# SheetPower.net
KiCad netlist of a schematic drawn in Altium Designer
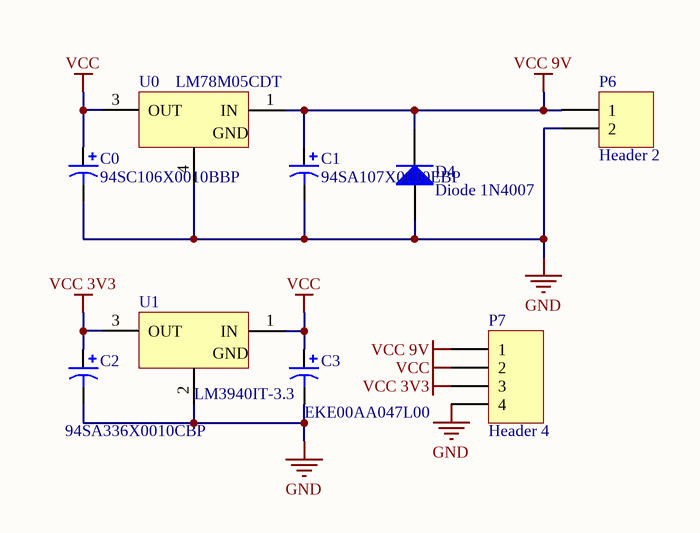
[diagram p0: SheetPower.SchDoc]

(export (version "E")
  (design (tool "Eeschema 10.0.6"))
  (components
    (comp (ref "C0")
      (value "94SC106X0010BBP")
      (footprint "B")
      (description "Solid Aluminum Capacitor with Organic Semiconductor Electrolyte: 10uF, 10V, Bulk Pack")
      (fields (field (name "PUBLISHER") "Altium Limited"))
      (libsource (lib "Vishay Electrolytic Radial-Lead Capacitor") (part "94SC106X0010BBP"))
    )
    (comp (ref "C1")
      (value "94SA107X0010EBP")
      (footprint "E")
      (description "Solid Aluminum Capacitor with Organic Semiconductor Electrolyte: 100uF, 10V, Bulk Pack")
      (fields (field (name "PUBLISHER") "Altium Limited"))
      (libsource (lib "Vishay Electrolytic Radial-Lead Capacitor") (part "94SA107X0010EBP"))
    )
    (comp (ref "C2")
      (value "94SA336X0010CBP")
      (footprint "C")
      (description "Solid Aluminum Capacitor with Organic Semiconductor Electrolyte: 33uF, 10V, Bulk Pack")
      (fields (field (name "PUBLISHER") "Altium Limited"))
      (libsource (lib "Vishay Electrolytic Radial-Lead Capacitor") (part "94SA336X0010CBP"))
    )
    (comp (ref "C3")
      (value "EKE00AA047L00")
      (footprint "CAPPR2-5X11")
      (description "Aluminum Electrolytic Capacitor, Radial Style with Long Leads: 470000pF, 100V")
      (fields (field (name "PUBLISHER") "Altium Limited"))
      (libsource (lib "Vishay Roederstein Electrolytic Radial-Lead Capacitor") (part "EKE00AA047L00"))
    )
    (comp (ref "D4")
      (value "Diode 1N4007")
      (footprint "DO-41")
      (description "1 Amp General Purpose Rectifier")
      (fields (field (name "PUBLISHER") "Altium Limited"))
      (libsource (lib "Miscellaneous Devices") (part "Diode 1N4007"))
    )
    (comp (ref "P6")
      (value "Header 2")
      (footprint "HDR1X2")
      (description "Header, 2-Pin")
      (fields (field (name "PUBLISHER") "Altium Limited"))
      (libsource (lib "Miscellaneous Connectors") (part "Header 2"))
    )
    (comp (ref "P7")
      (value "Header 4")
      (footprint "HDR1X4")
      (description "Header, 4-Pin")
      (fields (field (name "PUBLISHER") "Altium Limited"))
      (libsource (lib "Miscellaneous Connectors") (part "Header 4"))
    )
    (comp (ref "U0")
      (value "LM78M05CDT")
      (footprint "TD03B_L")
      (description "3-Terminal Positive Voltage Regulators, 3-pin TO-252")
      (fields
        (field (name "MANUFACTURER") "National Semiconductor")
        (field (name "PUBLISHER") "Altium Limited")
      )
      (libsource (lib "NSC LDO") (part "LM78M05CDT"))
    )
    (comp (ref "U1")
      (value "LM3940IT-3.3")
      (footprint "T03B")
      (description "1A Low Dropout Regulator for 5V to 3.3V Conversion, 3-pin TO-220")
      (fields
        (field (name "MANUFACTURER") "National Semiconductor")
        (field (name "PUBLISHER") "Altium Limited")
      )
      (libsource (lib "NSC LDO") (part "LM3940IT-3.3"))
    )
  )
  (nets
    (net (code "1") (name "GND") (class "Default")
      (node (ref "C0") (pin "2") (pinfunction "2_2") (pintype "passive"))
      (node (ref "C1") (pin "2") (pinfunction "2_2") (pintype "passive"))
      (node (ref "C2") (pin "2") (pinfunction "2_2") (pintype "passive"))
      (node (ref "C3") (pin "2") (pinfunction "2_2") (pintype "passive"))
      (node (ref "D4") (pin "1") (pinfunction "A_1") (pintype "passive"))
      (node (ref "P6") (pin "2") (pinfunction "2_2") (pintype "passive"))
      (node (ref "P7") (pin "4") (pinfunction "4_4") (pintype "passive"))
      (node (ref "U0") (pin "4") (pinfunction "GND_4") (pintype "power_in"))
      (node (ref "U1") (pin "2") (pinfunction "GND_2") (pintype "power_in"))
    )
    (net (code "2") (name "VCC") (class "Default")
      (node (ref "C0") (pin "1") (pinfunction "1_1") (pintype "passive"))
      (node (ref "C3") (pin "1") (pinfunction "1_1") (pintype "passive"))
      (node (ref "P7") (pin "2") (pinfunction "2_2") (pintype "passive"))
      (node (ref "U0") (pin "3") (pinfunction "OUT_3") (pintype "power_in"))
      (node (ref "U1") (pin "1") (pinfunction "IN_1") (pintype "power_in"))
    )
    (net (code "3") (name "VCC 3V3") (class "Default")
      (node (ref "C2") (pin "1") (pinfunction "1_1") (pintype "passive"))
      (node (ref "P7") (pin "3") (pinfunction "3_3") (pintype "passive"))
      (node (ref "U1") (pin "3") (pinfunction "OUT_3") (pintype "power_in"))
    )
    (net (code "4") (name "VCC 9V") (class "Default")
      (node (ref "C1") (pin "1") (pinfunction "1_1") (pintype "passive"))
      (node (ref "D4") (pin "2") (pinfunction "K_2") (pintype "passive"))
      (node (ref "P6") (pin "1") (pinfunction "1_1") (pintype "passive"))
      (node (ref "P7") (pin "1") (pinfunction "1_1") (pintype "passive"))
      (node (ref "U0") (pin "1") (pinfunction "IN_1") (pintype "power_in"))
    )
  )
)
